# PCB_2layers_editada_2607.net
KiCad netlist of a schematic drawn in EAGLE
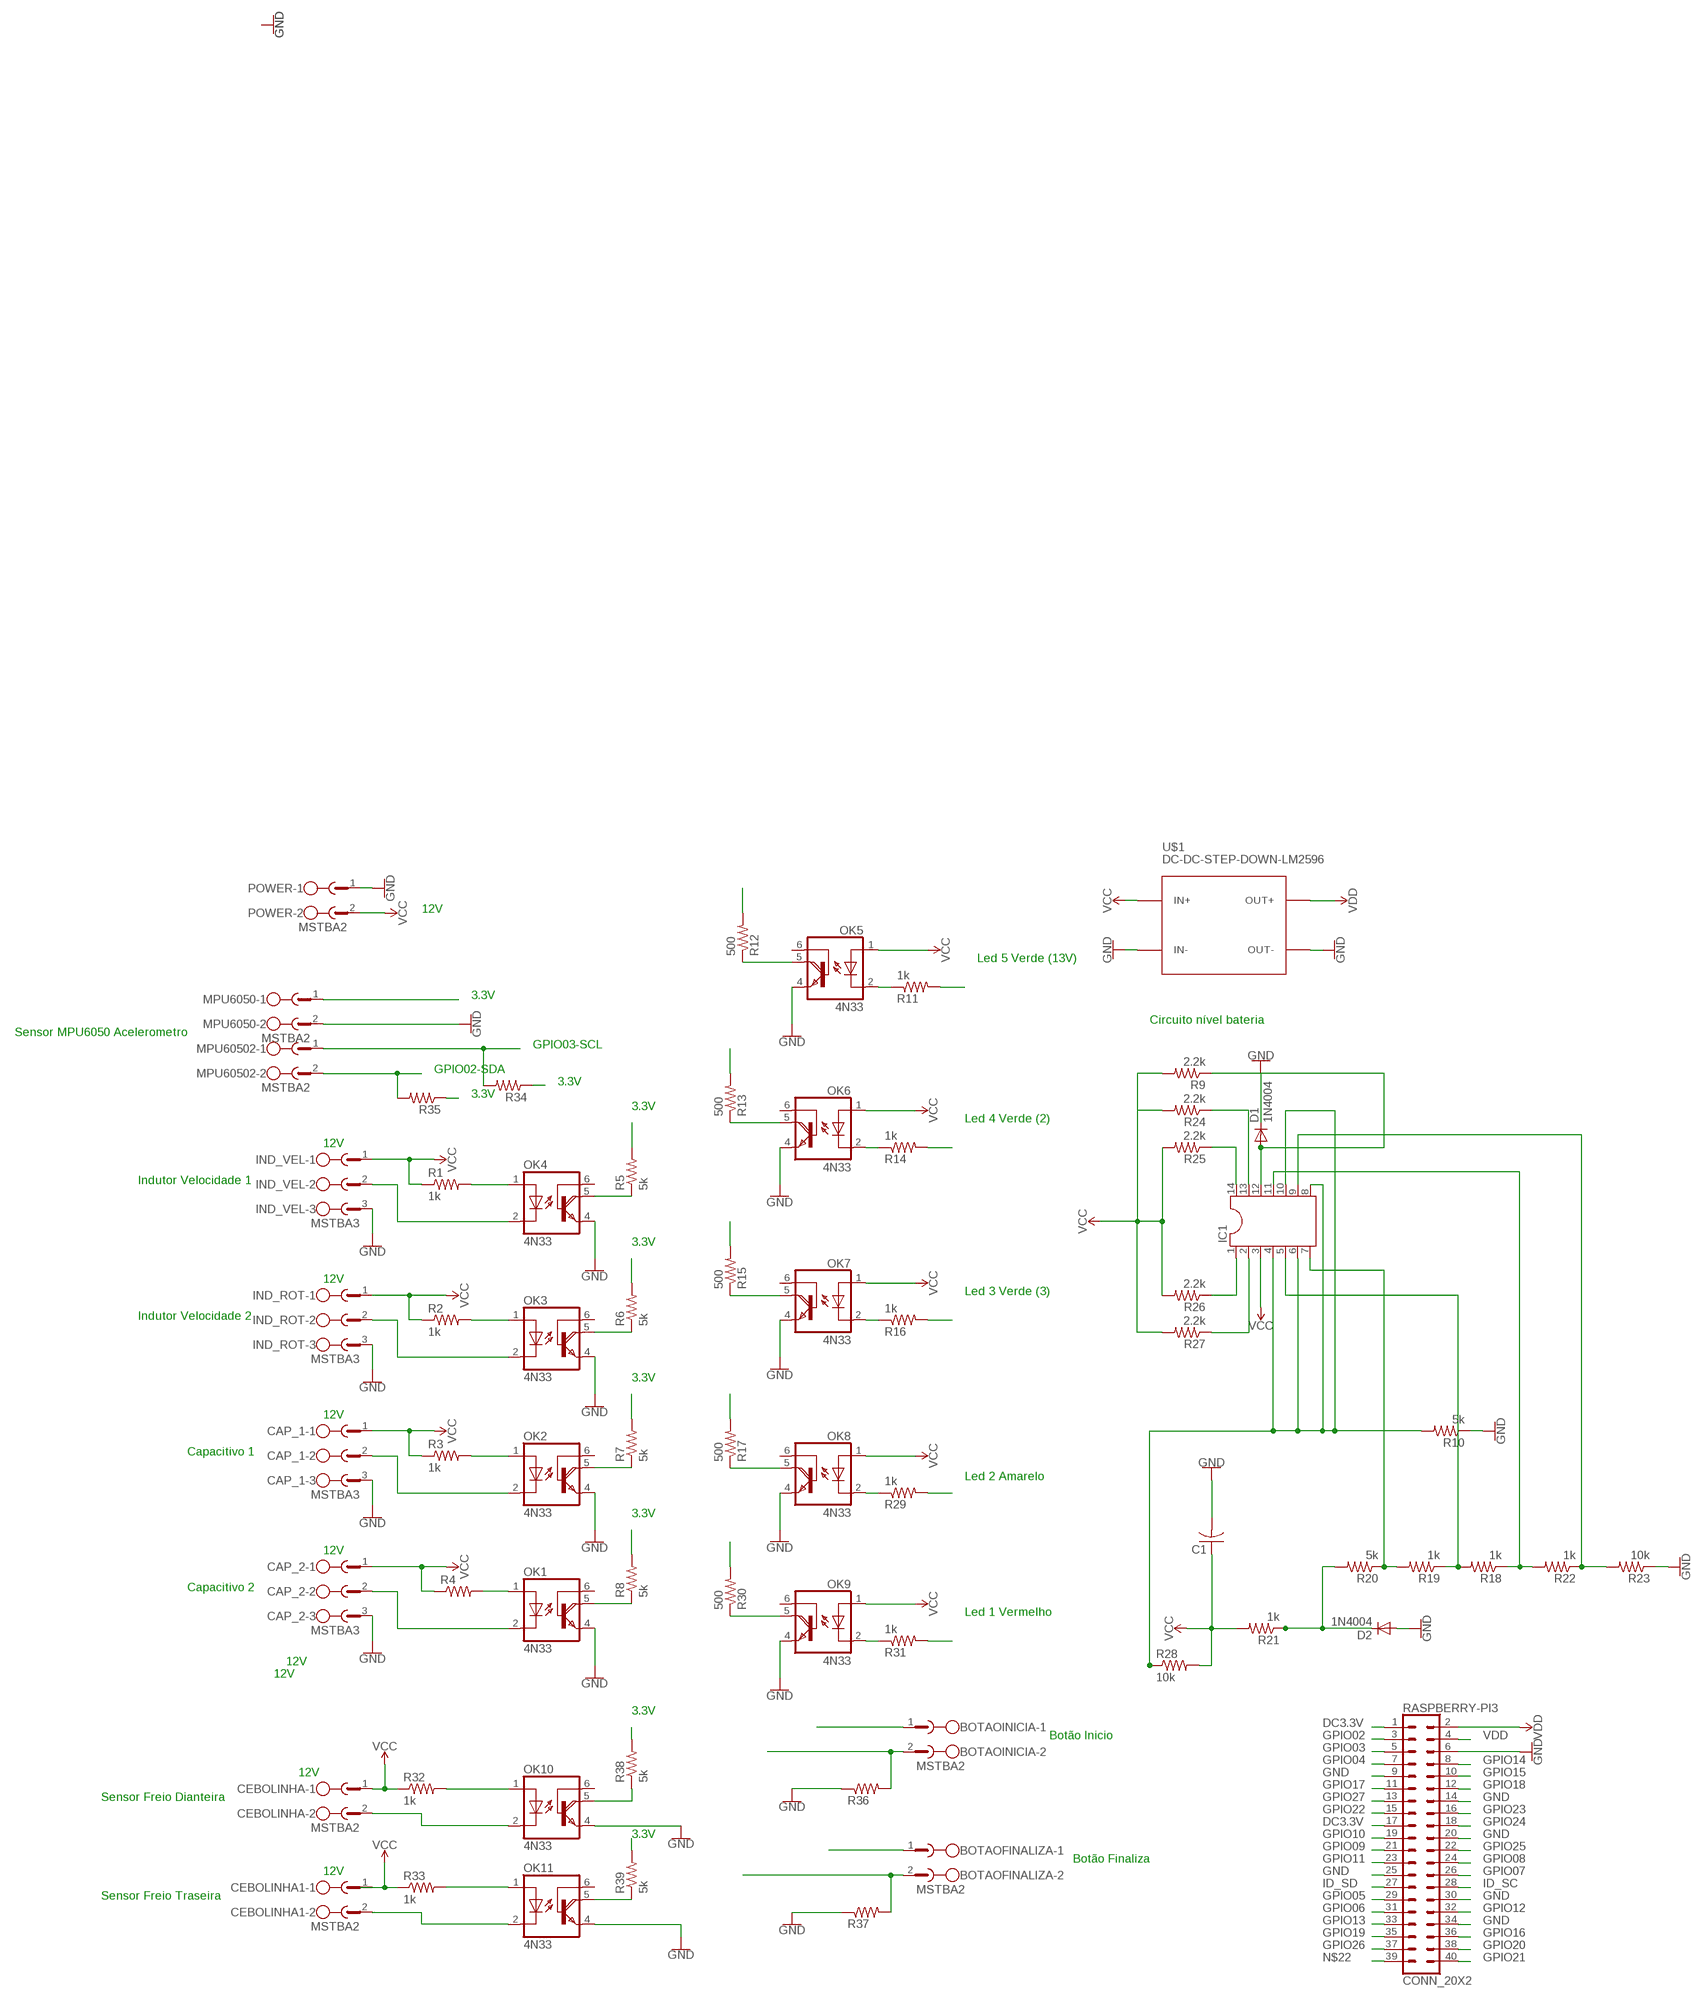
[diagram p0: schematic, sheet 1]

(export (version "E")
  (design (tool "Eeschema 10.0.6"))
  (components
    (comp (ref "BOTAOFINALIZA")
      (value "MSTBA2")
      (footprint "eagle-import:MSTBA2")
      (fields (field (name "MF") "FARNELL") (field (name "MPN") "1757242"))
      (libsource (lib "eagle-import") (part "MSTBA2"))
    )
    (comp (ref "BOTAOINICIA")
      (value "MSTBA2")
      (footprint "eagle-import:MSTBA2")
      (fields (field (name "MF") "FARNELL") (field (name "MPN") "1757242"))
      (libsource (lib "eagle-import") (part "MSTBA2"))
    )
    (comp (ref "C1")
      (value "C-US025-050X050")
      (footprint "eagle-import:C025-050X050")
      (libsource (lib "eagle-import") (part "C-US025-050X050"))
    )
    (comp (ref "CAP_1")
      (value "MSTBA3")
      (footprint "eagle-import:MSTBA3")
      (fields (field (name "MF") "FARNELL") (field (name "MPN") "1757255"))
      (libsource (lib "eagle-import") (part "MSTBA3"))
    )
    (comp (ref "CAP_2")
      (value "MSTBA3")
      (footprint "eagle-import:MSTBA3")
      (fields (field (name "MF") "FARNELL") (field (name "MPN") "1757255"))
      (libsource (lib "eagle-import") (part "MSTBA3"))
    )
    (comp (ref "CEBOLINHA")
      (value "MSTBA2")
      (footprint "eagle-import:MSTBA2")
      (fields (field (name "MF") "FARNELL") (field (name "MPN") "1757242"))
      (libsource (lib "eagle-import") (part "MSTBA2"))
    )
    (comp (ref "CEBOLINHA1")
      (value "MSTBA2")
      (footprint "eagle-import:MSTBA2")
      (fields (field (name "MF") "FARNELL") (field (name "MPN") "1757242"))
      (libsource (lib "eagle-import") (part "MSTBA2"))
    )
    (comp (ref "D1")
      (value "1N4004")
      (footprint "eagle-import:DO41-10")
      (libsource (lib "eagle-import") (part "1N4004"))
    )
    (comp (ref "D2")
      (value "1N4004")
      (footprint "eagle-import:DO41-10")
      (libsource (lib "eagle-import") (part "1N4004"))
    )
    (comp (ref "IC1")
      (value "DIL14")
      (footprint "eagle-import:DIL14")
      (libsource (lib "eagle-import") (part "DIL14"))
    )
    (comp (ref "IND_ROT")
      (value "MSTBA3")
      (footprint "eagle-import:MSTBA3")
      (fields (field (name "MF") "FARNELL") (field (name "MPN") "1757255"))
      (libsource (lib "eagle-import") (part "MSTBA3"))
    )
    (comp (ref "IND_VEL")
      (value "MSTBA3")
      (footprint "eagle-import:MSTBA3")
      (fields (field (name "MF") "FARNELL") (field (name "MPN") "1757255"))
      (libsource (lib "eagle-import") (part "MSTBA3"))
    )
    (comp (ref "MPU6050")
      (value "MSTBA2")
      (footprint "eagle-import:MSTBA2")
      (fields (field (name "MF") "FARNELL") (field (name "MPN") "1757242"))
      (libsource (lib "eagle-import") (part "MSTBA2"))
    )
    (comp (ref "MPU60502")
      (value "MSTBA2")
      (footprint "eagle-import:MSTBA2")
      (fields (field (name "MF") "FARNELL") (field (name "MPN") "1757242"))
      (libsource (lib "eagle-import") (part "MSTBA2"))
    )
    (comp (ref "OK1")
      (value "4N33")
      (footprint "eagle-import:DIL06")
      (fields (field (name "MF") "VISHAY/TELEFUNKEN"))
      (libsource (lib "eagle-import") (part "4N33"))
    )
    (comp (ref "OK2")
      (value "4N33")
      (footprint "eagle-import:DIL06")
      (fields (field (name "MF") "VISHAY/TELEFUNKEN"))
      (libsource (lib "eagle-import") (part "4N33"))
    )
    (comp (ref "OK3")
      (value "4N33")
      (footprint "eagle-import:DIL06")
      (fields (field (name "MF") "VISHAY/TELEFUNKEN"))
      (libsource (lib "eagle-import") (part "4N33"))
    )
    (comp (ref "OK4")
      (value "4N33")
      (footprint "eagle-import:DIL06")
      (fields (field (name "MF") "VISHAY/TELEFUNKEN"))
      (libsource (lib "eagle-import") (part "4N33"))
    )
    (comp (ref "OK5")
      (value "4N33")
      (footprint "eagle-import:DIL06")
      (fields (field (name "MF") "VISHAY/TELEFUNKEN"))
      (libsource (lib "eagle-import") (part "4N33"))
    )
    (comp (ref "OK6")
      (value "4N33")
      (footprint "eagle-import:DIL06")
      (fields (field (name "MF") "VISHAY/TELEFUNKEN"))
      (libsource (lib "eagle-import") (part "4N33"))
    )
    (comp (ref "OK7")
      (value "4N33")
      (footprint "eagle-import:DIL06")
      (fields (field (name "MF") "VISHAY/TELEFUNKEN"))
      (libsource (lib "eagle-import") (part "4N33"))
    )
    (comp (ref "OK8")
      (value "4N33")
      (footprint "eagle-import:DIL06")
      (fields (field (name "MF") "VISHAY/TELEFUNKEN"))
      (libsource (lib "eagle-import") (part "4N33"))
    )
    (comp (ref "OK9")
      (value "4N33")
      (footprint "eagle-import:DIL06")
      (fields (field (name "MF") "VISHAY/TELEFUNKEN"))
      (libsource (lib "eagle-import") (part "4N33"))
    )
    (comp (ref "OK10")
      (value "4N33")
      (footprint "eagle-import:DIL06")
      (fields (field (name "MF") "VISHAY/TELEFUNKEN"))
      (libsource (lib "eagle-import") (part "4N33"))
    )
    (comp (ref "OK11")
      (value "4N33")
      (footprint "eagle-import:DIL06")
      (fields (field (name "MF") "VISHAY/TELEFUNKEN"))
      (libsource (lib "eagle-import") (part "4N33"))
    )
    (comp (ref "POWER")
      (value "MSTBA2")
      (footprint "eagle-import:MSTBA2")
      (fields (field (name "MF") "FARNELL") (field (name "MPN") "1757242"))
      (libsource (lib "eagle-import") (part "MSTBA2"))
    )
    (comp (ref "R1")
      (value "1k")
      (footprint "eagle-import:0204_7")
      (libsource (lib "eagle-import") (part "rcl_334_R-US_0204/7"))
    )
    (comp (ref "R2")
      (value "1k")
      (footprint "eagle-import:0204_7")
      (libsource (lib "eagle-import") (part "rcl_334_R-US_0204/7"))
    )
    (comp (ref "R3")
      (value "1k")
      (footprint "eagle-import:0204_7")
      (libsource (lib "eagle-import") (part "rcl_334_R-US_0204/7"))
    )
    (comp (ref "R4")
      (value "R-US_0204/7")
      (footprint "eagle-import:0204_7")
      (libsource (lib "eagle-import") (part "rcl_334_R-US_0204/7"))
    )
    (comp (ref "R5")
      (value "5k")
      (footprint "eagle-import:0204_7")
      (libsource (lib "eagle-import") (part "rcl_334_R-US_0204/7"))
    )
    (comp (ref "R6")
      (value "5k")
      (footprint "eagle-import:0204_7")
      (libsource (lib "eagle-import") (part "rcl_334_R-US_0204/7"))
    )
    (comp (ref "R7")
      (value "5k")
      (footprint "eagle-import:0204_7")
      (libsource (lib "eagle-import") (part "rcl_334_R-US_0204/7"))
    )
    (comp (ref "R8")
      (value "5k")
      (footprint "eagle-import:0204_7")
      (libsource (lib "eagle-import") (part "rcl_334_R-US_0204/7"))
    )
    (comp (ref "R9")
      (value "2.2k")
      (footprint "eagle-import:0207_10")
      (libsource (lib "eagle-import") (part "R-US_0207/10"))
    )
    (comp (ref "R10")
      (value "5k")
      (footprint "eagle-import:0207_10")
      (libsource (lib "eagle-import") (part "R-US_0207/10"))
    )
    (comp (ref "R11")
      (value "1k")
      (footprint "eagle-import:0204_7")
      (libsource (lib "eagle-import") (part "rcl_334_R-US_0204/7"))
    )
    (comp (ref "R12")
      (value "500")
      (footprint "eagle-import:0204_7")
      (libsource (lib "eagle-import") (part "rcl_334_R-US_0204/7"))
    )
    (comp (ref "R13")
      (value "500")
      (footprint "eagle-import:0204_7")
      (libsource (lib "eagle-import") (part "rcl_334_R-US_0204/7"))
    )
    (comp (ref "R14")
      (value "1k")
      (footprint "eagle-import:0204_7")
      (libsource (lib "eagle-import") (part "rcl_334_R-US_0204/7"))
    )
    (comp (ref "R15")
      (value "500")
      (footprint "eagle-import:0204_7")
      (libsource (lib "eagle-import") (part "rcl_334_R-US_0204/7"))
    )
    (comp (ref "R16")
      (value "1k")
      (footprint "eagle-import:0204_7")
      (libsource (lib "eagle-import") (part "rcl_334_R-US_0204/7"))
    )
    (comp (ref "R17")
      (value "500")
      (footprint "eagle-import:0204_7")
      (libsource (lib "eagle-import") (part "rcl_334_R-US_0204/7"))
    )
    (comp (ref "R18")
      (value "1k")
      (footprint "eagle-import:0207_10")
      (libsource (lib "eagle-import") (part "R-US_0207/10"))
    )
    (comp (ref "R19")
      (value "1k")
      (footprint "eagle-import:0207_10")
      (libsource (lib "eagle-import") (part "R-US_0207/10"))
    )
    (comp (ref "R20")
      (value "5k")
      (footprint "eagle-import:0207_10")
      (libsource (lib "eagle-import") (part "R-US_0207/10"))
    )
    (comp (ref "R21")
      (value "1k")
      (footprint "eagle-import:0207_10")
      (libsource (lib "eagle-import") (part "R-US_0207/10"))
    )
    (comp (ref "R22")
      (value "1k")
      (footprint "eagle-import:0207_10")
      (libsource (lib "eagle-import") (part "R-US_0207/10"))
    )
    (comp (ref "R23")
      (value "10k")
      (footprint "eagle-import:0207_10")
      (libsource (lib "eagle-import") (part "R-US_0207/10"))
    )
    (comp (ref "R24")
      (value "2.2k")
      (footprint "eagle-import:0207_10")
      (libsource (lib "eagle-import") (part "R-US_0207/10"))
    )
    (comp (ref "R25")
      (value "2.2k")
      (footprint "eagle-import:0207_10")
      (libsource (lib "eagle-import") (part "R-US_0207/10"))
    )
    (comp (ref "R26")
      (value "2.2k")
      (footprint "eagle-import:0207_10")
      (libsource (lib "eagle-import") (part "R-US_0207/10"))
    )
    (comp (ref "R27")
      (value "2.2k")
      (footprint "eagle-import:0207_10")
      (libsource (lib "eagle-import") (part "R-US_0207/10"))
    )
    (comp (ref "R28")
      (value "10k")
      (footprint "eagle-import:0207_10")
      (libsource (lib "eagle-import") (part "R-US_0207/10"))
    )
    (comp (ref "R29")
      (value "1k")
      (footprint "eagle-import:0204_7")
      (libsource (lib "eagle-import") (part "rcl_334_R-US_0204/7"))
    )
    (comp (ref "R30")
      (value "500")
      (footprint "eagle-import:0204_7")
      (libsource (lib "eagle-import") (part "rcl_334_R-US_0204/7"))
    )
    (comp (ref "R31")
      (value "1k")
      (footprint "eagle-import:0204_7")
      (libsource (lib "eagle-import") (part "rcl_334_R-US_0204/7"))
    )
    (comp (ref "R32")
      (value "1k")
      (footprint "eagle-import:0204_7")
      (libsource (lib "eagle-import") (part "rcl_334_R-US_0204/7"))
    )
    (comp (ref "R33")
      (value "1k")
      (footprint "eagle-import:0204_7")
      (libsource (lib "eagle-import") (part "rcl_334_R-US_0204/7"))
    )
    (comp (ref "R34")
      (value "R-US_0204/7")
      (footprint "eagle-import:0204_7")
      (libsource (lib "eagle-import") (part "rcl_334_R-US_0204/7"))
    )
    (comp (ref "R35")
      (value "R-US_0204/7")
      (footprint "eagle-import:0204_7")
      (libsource (lib "eagle-import") (part "rcl_334_R-US_0204/7"))
    )
    (comp (ref "R36")
      (value "R-US_0204/7")
      (footprint "eagle-import:0204_7")
      (libsource (lib "eagle-import") (part "rcl_334_R-US_0204/7"))
    )
    (comp (ref "R37")
      (value "R-US_0204/7")
      (footprint "eagle-import:0204_7")
      (libsource (lib "eagle-import") (part "rcl_334_R-US_0204/7"))
    )
    (comp (ref "R38")
      (value "5k")
      (footprint "eagle-import:0204_7")
      (libsource (lib "eagle-import") (part "rcl_334_R-US_0204/7"))
    )
    (comp (ref "R39")
      (value "5k")
      (footprint "eagle-import:0204_7")
      (libsource (lib "eagle-import") (part "rcl_334_R-US_0204/7"))
    )
    (comp (ref "RASPBERRY-PI3")
      (value "CONN_20X2")
      (footprint "eagle-import:2X20")
      (libsource (lib "eagle-import") (part "CONN_20X2"))
    )
    (comp (ref "U$1")
      (value "DC-DC-STEP-DOWN-LM2596")
      (footprint "eagle-import:DC-DC-STEP-DOWN-LM2596")
      (libsource (lib "eagle-import") (part "DC-DC-STEP-DOWN-LM2596"))
    )
  )
  (nets
    (net (code "1") (name "/DC3.3V") (class "Default")
      (node (ref "BOTAOFINALIZA") (pin "1") (pinfunction "1_1") (pintype "passive"))
      (node (ref "BOTAOINICIA") (pin "1") (pinfunction "1_1") (pintype "passive"))
      (node (ref "MPU6050") (pin "1") (pinfunction "1_1") (pintype "passive"))
      (node (ref "R12") (pin "2") (pinfunction "2_2") (pintype "passive"))
      (node (ref "R13") (pin "2") (pinfunction "2_2") (pintype "passive"))
      (node (ref "R15") (pin "2") (pinfunction "2_2") (pintype "passive"))
      (node (ref "R17") (pin "2") (pinfunction "2_2") (pintype "passive"))
      (node (ref "R30") (pin "2") (pinfunction "2_2") (pintype "passive"))
      (node (ref "R34") (pin "1") (pinfunction "1_1") (pintype "passive"))
      (node (ref "R35") (pin "1") (pinfunction "1_1") (pintype "passive"))
      (node (ref "R38") (pin "2") (pinfunction "2_2") (pintype "passive"))
      (node (ref "R39") (pin "2") (pinfunction "2_2") (pintype "passive"))
      (node (ref "R5") (pin "2") (pinfunction "2_2") (pintype "passive"))
      (node (ref "R6") (pin "2") (pinfunction "2_2") (pintype "passive"))
      (node (ref "R7") (pin "2") (pinfunction "2_2") (pintype "passive"))
      (node (ref "R8") (pin "2") (pinfunction "2_2") (pintype "passive"))
      (node (ref "RASPBERRY-PI3") (pin "1") (pinfunction "1_1") (pintype "passive"))
      (node (ref "RASPBERRY-PI3") (pin "17") (pinfunction "17_17") (pintype "passive"))
    )
    (net (code "2") (name "/GPIO02") (class "Default")
      (node (ref "MPU60502") (pin "2") (pinfunction "1_2") (pintype "passive"))
      (node (ref "R35") (pin "2") (pinfunction "2_2") (pintype "passive"))
      (node (ref "RASPBERRY-PI3") (pin "3") (pinfunction "3_3") (pintype "passive"))
    )
    (net (code "3") (name "/GPIO03") (class "Default")
      (node (ref "MPU60502") (pin "1") (pinfunction "1_1") (pintype "passive"))
      (node (ref "R34") (pin "2") (pinfunction "2_2") (pintype "passive"))
      (node (ref "RASPBERRY-PI3") (pin "5") (pinfunction "5_5") (pintype "passive"))
    )
    (net (code "4") (name "/GPIO04") (class "Default")
      (node (ref "OK4") (pin "5") (pinfunction "COL_5") (pintype "passive"))
      (node (ref "R5") (pin "1") (pinfunction "1_1") (pintype "passive"))
      (node (ref "RASPBERRY-PI3") (pin "7") (pinfunction "7_7") (pintype "passive"))
    )
    (net (code "5") (name "/GPIO05") (class "Default")
      (node (ref "RASPBERRY-PI3") (pin "29") (pinfunction "29_29") (pintype "passive"))
    )
    (net (code "6") (name "/GPIO06") (class "Default")
      (node (ref "RASPBERRY-PI3") (pin "31") (pinfunction "31_31") (pintype "passive"))
    )
    (net (code "7") (name "/GPIO07") (class "Default")
      (node (ref "RASPBERRY-PI3") (pin "26") (pinfunction "26_26") (pintype "passive"))
    )
    (net (code "8") (name "/GPIO08") (class "Default")
      (node (ref "RASPBERRY-PI3") (pin "24") (pinfunction "24_24") (pintype "passive"))
    )
    (net (code "9") (name "/GPIO09") (class "Default")
      (node (ref "RASPBERRY-PI3") (pin "21") (pinfunction "21_21") (pintype "passive"))
    )
    (net (code "10") (name "/GPIO10") (class "Default")
      (node (ref "OK1") (pin "5") (pinfunction "COL_5") (pintype "passive"))
      (node (ref "R8") (pin "1") (pinfunction "1_1") (pintype "passive"))
      (node (ref "RASPBERRY-PI3") (pin "19") (pinfunction "19_19") (pintype "passive"))
    )
    (net (code "11") (name "/GPIO11") (class "Default")
      (node (ref "CEBOLINHA") (pin "2") (pinfunction "1_2") (pintype "passive"))
      (node (ref "OK10") (pin "2") (pinfunction "C_2") (pintype "passive"))
      (node (ref "RASPBERRY-PI3") (pin "23") (pinfunction "23_23") (pintype "passive"))
    )
    (net (code "12") (name "/GPIO12") (class "Default")
      (node (ref "RASPBERRY-PI3") (pin "32") (pinfunction "32_32") (pintype "passive"))
    )
    (net (code "13") (name "/GPIO13") (class "Default")
      (node (ref "RASPBERRY-PI3") (pin "33") (pinfunction "33_33") (pintype "passive"))
    )
    (net (code "14") (name "/GPIO14") (class "Default")
      (node (ref "OK5") (pin "5") (pinfunction "COL_5") (pintype "passive"))
      (node (ref "R12") (pin "1") (pinfunction "1_1") (pintype "passive"))
      (node (ref "RASPBERRY-PI3") (pin "8") (pinfunction "8_8") (pintype "passive"))
    )
    (net (code "15") (name "/GPIO15") (class "Default")
      (node (ref "OK6") (pin "5") (pinfunction "COL_5") (pintype "passive"))
      (node (ref "R13") (pin "1") (pinfunction "1_1") (pintype "passive"))
      (node (ref "RASPBERRY-PI3") (pin "10") (pinfunction "10_10") (pintype "passive"))
    )
    (net (code "16") (name "/GPIO16") (class "Default")
      (node (ref "BOTAOINICIA") (pin "2") (pinfunction "1_2") (pintype "passive"))
      (node (ref "R36") (pin "2") (pinfunction "2_2") (pintype "passive"))
      (node (ref "RASPBERRY-PI3") (pin "36") (pinfunction "36_36") (pintype "passive"))
    )
    (net (code "17") (name "/GPIO17") (class "Default")
      (node (ref "OK3") (pin "5") (pinfunction "COL_5") (pintype "passive"))
      (node (ref "R6") (pin "1") (pinfunction "1_1") (pintype "passive"))
      (node (ref "RASPBERRY-PI3") (pin "11") (pinfunction "11_11") (pintype "passive"))
    )
    (net (code "18") (name "/GPIO18") (class "Default")
      (node (ref "OK7") (pin "5") (pinfunction "COL_5") (pintype "passive"))
      (node (ref "R15") (pin "1") (pinfunction "1_1") (pintype "passive"))
      (node (ref "RASPBERRY-PI3") (pin "12") (pinfunction "12_12") (pintype "passive"))
    )
    (net (code "19") (name "/GPIO19") (class "Default")
      (node (ref "OK10") (pin "5") (pinfunction "COL_5") (pintype "passive"))
      (node (ref "R38") (pin "1") (pinfunction "1_1") (pintype "passive"))
      (node (ref "RASPBERRY-PI3") (pin "35") (pinfunction "35_35") (pintype "passive"))
    )
    (net (code "20") (name "/GPIO20") (class "Default")
      (node (ref "BOTAOFINALIZA") (pin "2") (pinfunction "1_2") (pintype "passive"))
      (node (ref "R37") (pin "2") (pinfunction "2_2") (pintype "passive"))
      (node (ref "RASPBERRY-PI3") (pin "38") (pinfunction "38_38") (pintype "passive"))
    )
    (net (code "21") (name "/GPIO21") (class "Default")
      (node (ref "RASPBERRY-PI3") (pin "40") (pinfunction "40_40") (pintype "passive"))
    )
    (net (code "22") (name "/GPIO22") (class "Default")
      (node (ref "OK2") (pin "5") (pinfunction "COL_5") (pintype "passive"))
      (node (ref "R7") (pin "1") (pinfunction "1_1") (pintype "passive"))
      (node (ref "RASPBERRY-PI3") (pin "15") (pinfunction "15_15") (pintype "passive"))
    )
    (net (code "23") (name "/GPIO23") (class "Default")
      (node (ref "OK8") (pin "5") (pinfunction "COL_5") (pintype "passive"))
      (node (ref "R17") (pin "1") (pinfunction "1_1") (pintype "passive"))
      (node (ref "RASPBERRY-PI3") (pin "16") (pinfunction "16_16") (pintype "passive"))
    )
    (net (code "24") (name "/GPIO24") (class "Default")
      (node (ref "OK9") (pin "5") (pinfunction "COL_5") (pintype "passive"))
      (node (ref "R30") (pin "1") (pinfunction "1_1") (pintype "passive"))
      (node (ref "RASPBERRY-PI3") (pin "18") (pinfunction "18_18") (pintype "passive"))
    )
    (net (code "25") (name "/GPIO25") (class "Default")
      (node (ref "RASPBERRY-PI3") (pin "22") (pinfunction "22_22") (pintype "passive"))
    )
    (net (code "26") (name "/GPIO26") (class "Default")
      (node (ref "OK11") (pin "5") (pinfunction "COL_5") (pintype "passive"))
      (node (ref "R39") (pin "1") (pinfunction "1_1") (pintype "passive"))
      (node (ref "RASPBERRY-PI3") (pin "37") (pinfunction "37_37") (pintype "passive"))
    )
    (net (code "27") (name "/GPIO27") (class "Default")
      (node (ref "RASPBERRY-PI3") (pin "13") (pinfunction "13_13") (pintype "passive"))
    )
    (net (code "28") (name "/ID_SC") (class "Default")
      (node (ref "RASPBERRY-PI3") (pin "28") (pinfunction "28_28") (pintype "passive"))
    )
    (net (code "29") (name "/ID_SD") (class "Default")
      (node (ref "RASPBERRY-PI3") (pin "27") (pinfunction "27_27") (pintype "passive"))
    )
    (net (code "30") (name "/LM339P1") (class "Default")
      (node (ref "IC1") (pin "1") (pinfunction "1_1") (pintype "passive"))
      (node (ref "R11") (pin "2") (pinfunction "2_2") (pintype "passive"))
      (node (ref "R26") (pin "1") (pinfunction "1_1") (pintype "passive"))
    )
    (net (code "31") (name "/LM339P2") (class "Default")
      (node (ref "IC1") (pin "2") (pinfunction "2_2") (pintype "passive"))
      (node (ref "R14") (pin "2") (pinfunction "2_2") (pintype "passive"))
      (node (ref "R27") (pin "1") (pinfunction "1_1") (pintype "passive"))
    )
    (net (code "32") (name "/LM339P13") (class "Default")
      (node (ref "IC1") (pin "13") (pinfunction "13_13") (pintype "passive"))
      (node (ref "R16") (pin "2") (pinfunction "2_2") (pintype "passive"))
      (node (ref "R24") (pin "1") (pinfunction "1_1") (pintype "passive"))
    )
    (net (code "33") (name "/LM339P14") (class "Default")
      (node (ref "IC1") (pin "14") (pinfunction "14_14") (pintype "passive"))
      (node (ref "R25") (pin "1") (pinfunction "1_1") (pintype "passive"))
      (node (ref "R29") (pin "2") (pinfunction "2_2") (pintype "passive"))
    )
    (net (code "34") (name "/N$22") (class "Default")
      (node (ref "RASPBERRY-PI3") (pin "39") (pinfunction "39_39") (pintype "passive"))
    )
    (net (code "35") (name "GND") (class "Default")
      (node (ref "C1") (pin "2") (pinfunction "2_2") (pintype "passive"))
      (node (ref "CAP_1") (pin "3") (pinfunction "1_3") (pintype "passive"))
      (node (ref "CAP_2") (pin "3") (pinfunction "1_3") (pintype "passive"))
      (node (ref "D1") (pin "C") (pinfunction "C_C") (pintype "passive"))
      (node (ref "D2") (pin "A") (pinfunction "A_A") (pintype "passive"))
      (node (ref "IND_ROT") (pin "3") (pinfunction "1_3") (pintype "passive"))
      (node (ref "IND_VEL") (pin "3") (pinfunction "1_3") (pintype "passive"))
      (node (ref "MPU6050") (pin "2") (pinfunction "1_2") (pintype "passive"))
      (node (ref "OK1") (pin "4") (pinfunction "E_4") (pintype "passive"))
      (node (ref "OK10") (pin "4") (pinfunction "E_4") (pintype "passive"))
      (node (ref "OK11") (pin "4") (pinfunction "E_4") (pintype "passive"))
      (node (ref "OK2") (pin "4") (pinfunction "E_4") (pintype "passive"))
      (node (ref "OK3") (pin "4") (pinfunction "E_4") (pintype "passive"))
      (node (ref "OK4") (pin "4") (pinfunction "E_4") (pintype "passive"))
      (node (ref "OK5") (pin "4") (pinfunction "E_4") (pintype "passive"))
      (node (ref "OK6") (pin "4") (pinfunction "E_4") (pintype "passive"))
      (node (ref "OK7") (pin "4") (pinfunction "E_4") (pintype "passive"))
      (node (ref "OK8") (pin "4") (pinfunction "E_4") (pintype "passive"))
      (node (ref "OK9") (pin "4") (pinfunction "E_4") (pintype "passive"))
      (node (ref "POWER") (pin "1") (pinfunction "1_1") (pintype "passive"))
      (node (ref "R10") (pin "1") (pinfunction "1_1") (pintype "passive"))
      (node (ref "R23") (pin "1") (pinfunction "1_1") (pintype "passive"))
      (node (ref "R36") (pin "1") (pinfunction "1_1") (pintype "passive"))
      (node (ref "R37") (pin "1") (pinfunction "1_1") (pintype "passive"))
      (node (ref "RASPBERRY-PI3") (pin "14") (pinfunction "14_14") (pintype "passive"))
      (node (ref "RASPBERRY-PI3") (pin "20") (pinfunction "20_20") (pintype "passive"))
      (node (ref "RASPBERRY-PI3") (pin "25") (pinfunction "25_25") (pintype "passive"))
      (node (ref "RASPBERRY-PI3") (pin "30") (pinfunction "30_30") (pintype "passive"))
      (node (ref "RASPBERRY-PI3") (pin "34") (pinfunction "34_34") (pintype "passive"))
      (node (ref "RASPBERRY-PI3") (pin "6") (pinfunction "6_6") (pintype "passive"))
      (node (ref "RASPBERRY-PI3") (pin "9") (pinfunction "9_9") (pintype "passive"))
      (node (ref "U$1") (pin "IN-") (pinfunction "IN-_IN-") (pintype "bidirectional"))
      (node (ref "U$1") (pin "OUT-") (pinfunction "OUT-_OUT-") (pintype "bidirectional"))
    )
    (net (code "36") (name "Net-(CAP_1B-1)") (class "Default")
      (node (ref "CAP_1") (pin "2") (pinfunction "1_2") (pintype "passive"))
      (node (ref "OK2") (pin "2") (pinfunction "C_2") (pintype "passive"))
    )
    (net (code "37") (name "Net-(CAP_2B-1)") (class "Default")
      (node (ref "CAP_2") (pin "2") (pinfunction "1_2") (pintype "passive"))
      (node (ref "OK1") (pin "2") (pinfunction "C_2") (pintype "passive"))
    )
    (net (code "38") (name "Net-(CEBOLINHA1B-1)") (class "Default")
      (node (ref "CEBOLINHA1") (pin "2") (pinfunction "1_2") (pintype "passive"))
      (node (ref "OK11") (pin "2") (pinfunction "C_2") (pintype "passive"))
    )
    (net (code "39") (name "Net-(D1-PadA)") (class "Default")
      (node (ref "D1") (pin "A") (pinfunction "A_A") (pintype "passive"))
      (node (ref "IC1") (pin "12") (pinfunction "12_12") (pintype "passive"))
      (node (ref "R9") (pin "1") (pinfunction "1_1") (pintype "passive"))
    )
    (net (code "40") (name "Net-(D2-PadC)") (class "Default")
      (node (ref "D2") (pin "C") (pinfunction "C_C") (pintype "passive"))
      (node (ref "R20") (pin "2") (pinfunction "2_2") (pintype "passive"))
      (node (ref "R21") (pin "1") (pinfunction "1_1") (pintype "passive"))
    )
    (net (code "41") (name "Net-(IC1-Pad5)") (class "Default")
      (node (ref "IC1") (pin "5") (pinfunction "5_5") (pintype "passive"))
      (node (ref "R18") (pin "2") (pinfunction "2_2") (pintype "passive"))
      (node (ref "R19") (pin "1") (pinfunction "1_1") (pintype "passive"))
    )
    (net (code "42") (name "Net-(IC1-Pad7)") (class "Default")
      (node (ref "IC1") (pin "7") (pinfunction "7_7") (pintype "passive"))
      (node (ref "R19") (pin "2") (pinfunction "2_2") (pintype "passive"))
      (node (ref "R20") (pin "1") (pinfunction "1_1") (pintype "passive"))
    )
    (net (code "43") (name "Net-(IC1-Pad9)") (class "Default")
      (node (ref "IC1") (pin "9") (pinfunction "9_9") (pintype "passive"))
      (node (ref "R22") (pin "1") (pinfunction "1_1") (pintype "passive"))
      (node (ref "R23") (pin "2") (pinfunction "2_2") (pintype "passive"))
    )
    (net (code "44") (name "Net-(IC1-Pad10)") (class "Default")
      (node (ref "IC1") (pin "10") (pinfunction "10_10") (pintype "passive"))
      (node (ref "IC1") (pin "4") (pinfunction "4_4") (pintype "passive"))
      (node (ref "IC1") (pin "6") (pinfunction "6_6") (pintype "passive"))
      (node (ref "IC1") (pin "8") (pinfunction "8_8") (pintype "passive"))
      (node (ref "R10") (pin "2") (pinfunction "2_2") (pintype "passive"))
      (node (ref "R28") (pin "1") (pinfunction "1_1") (pintype "passive"))
    )
    (net (code "45") (name "Net-(IC1-Pad11)") (class "Default")
      (node (ref "IC1") (pin "11") (pinfunction "11_11") (pintype "passive"))
      (node (ref "R18") (pin "1") (pinfunction "1_1") (pintype "passive"))
      (node (ref "R22") (pin "2") (pinfunction "2_2") (pintype "passive"))
    )
    (net (code "46") (name "Net-(IND_ROTB-1)") (class "Default")
      (node (ref "IND_ROT") (pin "2") (pinfunction "1_2") (pintype "passive"))
      (node (ref "OK3") (pin "2") (pinfunction "C_2") (pintype "passive"))
    )
    (net (code "47") (name "Net-(IND_VELB-1)") (class "Default")
      (node (ref "IND_VEL") (pin "2") (pinfunction "1_2") (pintype "passive"))
      (node (ref "OK4") (pin "2") (pinfunction "C_2") (pintype "passive"))
    )
    (net (code "48") (name "Net-(OK1-A)") (class "Default")
      (node (ref "OK1") (pin "1") (pinfunction "A_1") (pintype "passive"))
      (node (ref "R4") (pin "2") (pinfunction "2_2") (pintype "passive"))
    )
    (net (code "49") (name "Net-(OK2-A)") (class "Default")
      (node (ref "OK2") (pin "1") (pinfunction "A_1") (pintype "passive"))
      (node (ref "R3") (pin "2") (pinfunction "2_2") (pintype "passive"))
    )
    (net (code "50") (name "Net-(OK3-A)") (class "Default")
      (node (ref "OK3") (pin "1") (pinfunction "A_1") (pintype "passive"))
      (node (ref "R2") (pin "2") (pinfunction "2_2") (pintype "passive"))
    )
    (net (code "51") (name "Net-(OK4-A)") (class "Default")
      (node (ref "OK4") (pin "1") (pinfunction "A_1") (pintype "passive"))
      (node (ref "R1") (pin "2") (pinfunction "2_2") (pintype "passive"))
    )
    (net (code "52") (name "Net-(OK5-C)") (class "Default")
      (node (ref "OK5") (pin "2") (pinfunction "C_2") (pintype "passive"))
      (node (ref "R11") (pin "1") (pinfunction "1_1") (pintype "passive"))
    )
    (net (code "53") (name "Net-(OK6-C)") (class "Default")
      (node (ref "OK6") (pin "2") (pinfunction "C_2") (pintype "passive"))
      (node (ref "R14") (pin "1") (pinfunction "1_1") (pintype "passive"))
    )
    (net (code "54") (name "Net-(OK7-C)") (class "Default")
      (node (ref "OK7") (pin "2") (pinfunction "C_2") (pintype "passive"))
      (node (ref "R16") (pin "1") (pinfunction "1_1") (pintype "passive"))
    )
    (net (code "55") (name "Net-(OK8-C)") (class "Default")
      (node (ref "OK8") (pin "2") (pinfunction "C_2") (pintype "passive"))
      (node (ref "R29") (pin "1") (pinfunction "1_1") (pintype "passive"))
    )
    (net (code "56") (name "Net-(OK9-C)") (class "Default")
      (node (ref "OK9") (pin "2") (pinfunction "C_2") (pintype "passive"))
      (node (ref "R31") (pin "1") (pinfunction "1_1") (pintype "passive"))
    )
    (net (code "57") (name "Net-(OK10-A)") (class "Default")
      (node (ref "OK10") (pin "1") (pinfunction "A_1") (pintype "passive"))
      (node (ref "R32") (pin "2") (pinfunction "2_2") (pintype "passive"))
    )
    (net (code "58") (name "Net-(OK11-A)") (class "Default")
      (node (ref "OK11") (pin "1") (pinfunction "A_1") (pintype "passive"))
      (node (ref "R33") (pin "2") (pinfunction "2_2") (pintype "passive"))
    )
    (net (code "59") (name "VCC") (class "Default")
      (node (ref "C1") (pin "1") (pinfunction "1_1") (pintype "passive"))
      (node (ref "CAP_1") (pin "1") (pinfunction "1_1") (pintype "passive"))
      (node (ref "CAP_2") (pin "1") (pinfunction "1_1") (pintype "passive"))
      (node (ref "CEBOLINHA") (pin "1") (pinfunction "1_1") (pintype "passive"))
      (node (ref "CEBOLINHA1") (pin "1") (pinfunction "1_1") (pintype "passive"))
      (node (ref "IC1") (pin "3") (pinfunction "3_3") (pintype "passive"))
      (node (ref "IND_ROT") (pin "1") (pinfunction "1_1") (pintype "passive"))
      (node (ref "IND_VEL") (pin "1") (pinfunction "1_1") (pintype "passive"))
      (node (ref "OK5") (pin "1") (pinfunction "A_1") (pintype "passive"))
      (node (ref "OK6") (pin "1") (pinfunction "A_1") (pintype "passive"))
      (node (ref "OK7") (pin "1") (pinfunction "A_1") (pintype "passive"))
      (node (ref "OK8") (pin "1") (pinfunction "A_1") (pintype "passive"))
      (node (ref "OK9") (pin "1") (pinfunction "A_1") (pintype "passive"))
      (node (ref "POWER") (pin "2") (pinfunction "1_2") (pintype "passive"))
      (node (ref "R1") (pin "1") (pinfunction "1_1") (pintype "passive"))
      (node (ref "R2") (pin "1") (pinfunction "1_1") (pintype "passive"))
      (node (ref "R21") (pin "2") (pinfunction "2_2") (pintype "passive"))
      (node (ref "R24") (pin "2") (pinfunction "2_2") (pintype "passive"))
      (node (ref "R25") (pin "2") (pinfunction "2_2") (pintype "passive"))
      (node (ref "R26") (pin "2") (pinfunction "2_2") (pintype "passive"))
      (node (ref "R27") (pin "2") (pinfunction "2_2") (pintype "passive"))
      (node (ref "R28") (pin "2") (pinfunction "2_2") (pintype "passive"))
      (node (ref "R3") (pin "1") (pinfunction "1_1") (pintype "passive"))
      (node (ref "R32") (pin "1") (pinfunction "1_1") (pintype "passive"))
      (node (ref "R33") (pin "1") (pinfunction "1_1") (pintype "passive"))
      (node (ref "R4") (pin "1") (pinfunction "1_1") (pintype "passive"))
      (node (ref "R9") (pin "2") (pinfunction "2_2") (pintype "passive"))
      (node (ref "U$1") (pin "IN+") (pinfunction "IN+_IN+") (pintype "bidirectional"))
    )
    (net (code "60") (name "VDD") (class "Default")
      (node (ref "RASPBERRY-PI3") (pin "2") (pinfunction "2_2") (pintype "passive"))
      (node (ref "RASPBERRY-PI3") (pin "4") (pinfunction "4_4") (pintype "passive"))
      (node (ref "U$1") (pin "OUT+") (pinfunction "OUT+_OUT+") (pintype "bidirectional"))
    )
    (net (code "61") (name "unconnected-(OK1-B-Pad6)") (class "Default")
      (node (ref "OK1") (pin "6") (pinfunction "B_6") (pintype "passive"))
    )
    (net (code "62") (name "unconnected-(OK2-B-Pad6)") (class "Default")
      (node (ref "OK2") (pin "6") (pinfunction "B_6") (pintype "passive"))
    )
    (net (code "63") (name "unconnected-(OK3-B-Pad6)") (class "Default")
      (node (ref "OK3") (pin "6") (pinfunction "B_6") (pintype "passive"))
    )
    (net (code "64") (name "unconnected-(OK4-B-Pad6)") (class "Default")
      (node (ref "OK4") (pin "6") (pinfunction "B_6") (pintype "passive"))
    )
    (net (code "65") (name "unconnected-(OK5-B-Pad6)") (class "Default")
      (node (ref "OK5") (pin "6") (pinfunction "B_6") (pintype "passive"))
    )
    (net (code "66") (name "unconnected-(OK6-B-Pad6)") (class "Default")
      (node (ref "OK6") (pin "6") (pinfunction "B_6") (pintype "passive"))
    )
    (net (code "67") (name "unconnected-(OK7-B-Pad6)") (class "Default")
      (node (ref "OK7") (pin "6") (pinfunction "B_6") (pintype "passive"))
    )
    (net (code "68") (name "unconnected-(OK8-B-Pad6)") (class "Default")
      (node (ref "OK8") (pin "6") (pinfunction "B_6") (pintype "passive"))
    )
    (net (code "69") (name "unconnected-(OK9-B-Pad6)") (class "Default")
      (node (ref "OK9") (pin "6") (pinfunction "B_6") (pintype "passive"))
    )
    (net (code "70") (name "unconnected-(OK10-B-Pad6)") (class "Default")
      (node (ref "OK10") (pin "6") (pinfunction "B_6") (pintype "passive"))
    )
    (net (code "71") (name "unconnected-(OK11-B-Pad6)") (class "Default")
      (node (ref "OK11") (pin "6") (pinfunction "B_6") (pintype "passive"))
    )
    (net (code "72") (name "unconnected-(R31-Pad2)") (class "Default")
      (node (ref "R31") (pin "2") (pinfunction "2_2") (pintype "passive"))
    )
  )
)
